# H-bridge.net
KiCad netlist of a schematic drawn in EAGLE
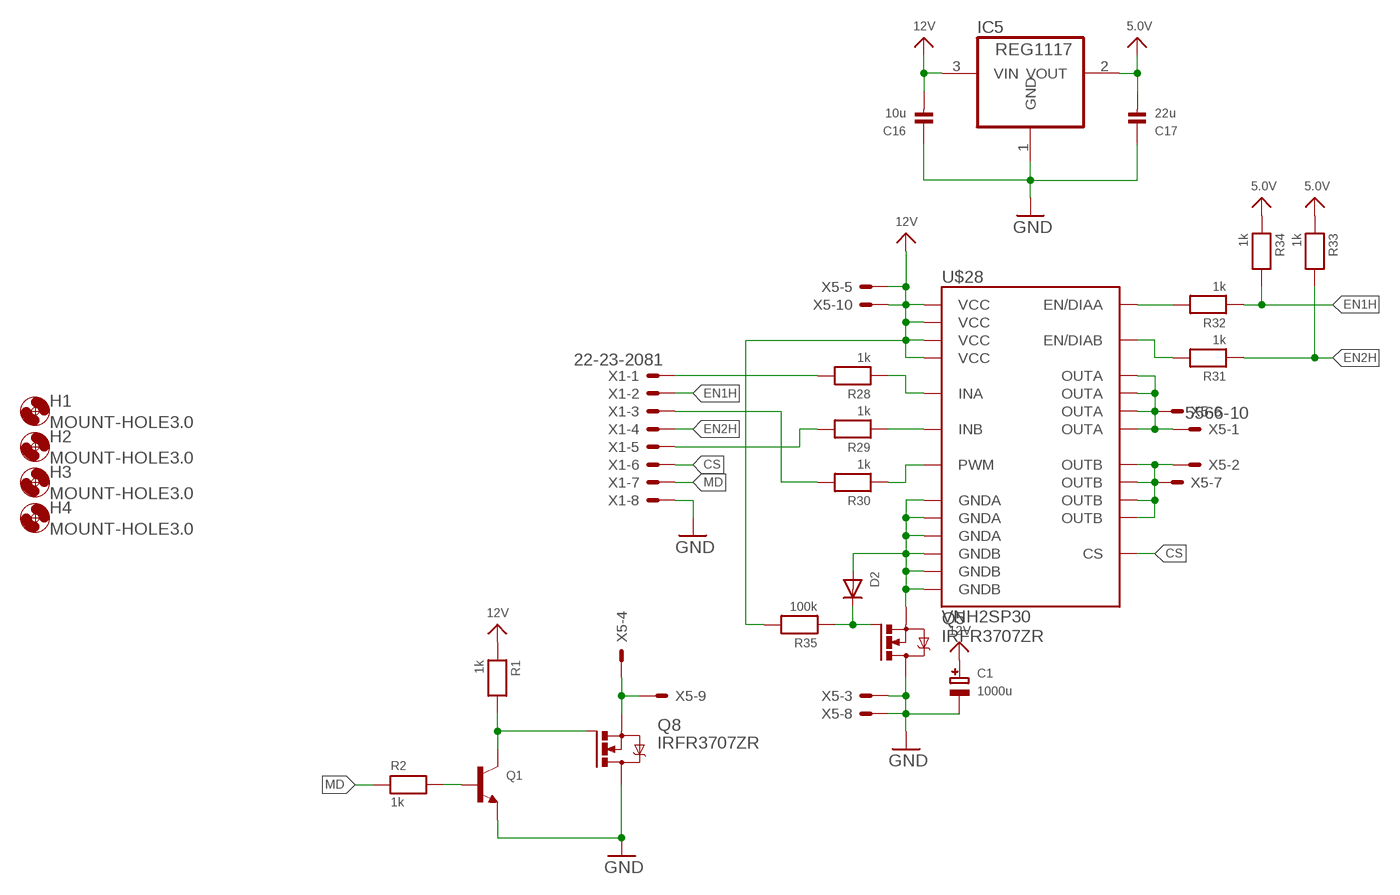
[diagram p0: schematic, sheet 1]

(export (version "E")
  (design (tool "Eeschema 10.0.6"))
  (components
    (comp (ref "C1")
      (value "1000u")
      (footprint "eagle-import:CELEC_3.5MM_10MM")
      (libsource (lib "eagle-import") (part "CAP_ELECTROLYTICPTH_3.5MMGRID_10MMDIA"))
    )
    (comp (ref "C16")
      (value "10u")
      (footprint "eagle-import:_0805")
      (libsource (lib "eagle-import") (part "CAP_CERAMIC_0805"))
    )
    (comp (ref "C17")
      (value "22u")
      (footprint "eagle-import:_0805")
      (libsource (lib "eagle-import") (part "CAP_CERAMIC_0805"))
    )
    (comp (ref "D2")
      (value "DIODESMA")
      (footprint "eagle-import:SMADIODE")
      (libsource (lib "eagle-import") (part "DIODESMA"))
    )
    (comp (ref "H1")
      (value "MOUNT-HOLE3.0")
      (footprint "eagle-import:3,0")
      (libsource (lib "eagle-import") (part "MOUNT-HOLE3.0"))
    )
    (comp (ref "H2")
      (value "MOUNT-HOLE3.0")
      (footprint "eagle-import:3,0")
      (libsource (lib "eagle-import") (part "MOUNT-HOLE3.0"))
    )
    (comp (ref "H3")
      (value "MOUNT-HOLE3.0")
      (footprint "eagle-import:3,0")
      (libsource (lib "eagle-import") (part "MOUNT-HOLE3.0"))
    )
    (comp (ref "H4")
      (value "MOUNT-HOLE3.0")
      (footprint "eagle-import:3,0")
      (libsource (lib "eagle-import") (part "MOUNT-HOLE3.0"))
    )
    (comp (ref "IC5")
      (value "REG1117")
      (footprint "eagle-import:SOT223")
      (libsource (lib "eagle-import") (part "REG1117"))
    )
    (comp (ref "Q1")
      (value "TRANSISTOR_NPNWIDE")
      (footprint "eagle-import:SOT23-WIDE")
      (libsource (lib "eagle-import") (part "TRANSISTOR_NPNWIDE"))
    )
    (comp (ref "Q5")
      (value "IRFR3707ZR")
      (footprint "eagle-import:D-PAK_TO252AA")
      (libsource (lib "eagle-import") (part "IRFR3707ZR"))
    )
    (comp (ref "Q8")
      (value "IRFR3707ZR")
      (footprint "eagle-import:D-PAK_TO252AA")
      (libsource (lib "eagle-import") (part "IRFR3707ZR"))
    )
    (comp (ref "R1")
      (value "1k")
      (footprint "eagle-import:_0603")
      (libsource (lib "eagle-import") (part "RESISTOR_0603"))
    )
    (comp (ref "R2")
      (value "1k")
      (footprint "eagle-import:_0603")
      (libsource (lib "eagle-import") (part "RESISTOR_0603"))
    )
    (comp (ref "R28")
      (value "1k")
      (footprint "eagle-import:_0603")
      (libsource (lib "eagle-import") (part "RESISTOR_0603"))
    )
    (comp (ref "R29")
      (value "1k")
      (footprint "eagle-import:_0603")
      (libsource (lib "eagle-import") (part "RESISTOR_0603"))
    )
    (comp (ref "R30")
      (value "1k")
      (footprint "eagle-import:_0603")
      (libsource (lib "eagle-import") (part "RESISTOR_0603"))
    )
    (comp (ref "R31")
      (value "1k")
      (footprint "eagle-import:_0603")
      (libsource (lib "eagle-import") (part "RESISTOR_0603"))
    )
    (comp (ref "R32")
      (value "1k")
      (footprint "eagle-import:_0603")
      (libsource (lib "eagle-import") (part "RESISTOR_0603"))
    )
    (comp (ref "R33")
      (value "1k")
      (footprint "eagle-import:_0603")
      (libsource (lib "eagle-import") (part "RESISTOR_0603"))
    )
    (comp (ref "R34")
      (value "1k")
      (footprint "eagle-import:_0603")
      (libsource (lib "eagle-import") (part "RESISTOR_0603"))
    )
    (comp (ref "R35")
      (value "100k")
      (footprint "eagle-import:_0603")
      (libsource (lib "eagle-import") (part "RESISTOR_0603"))
    )
    (comp (ref "U$28")
      (value "VNH2SP30")
      (footprint "eagle-import:VNH2SP30")
      (libsource (lib "eagle-import") (part "VNH2SP30"))
    )
    (comp (ref "X1")
      (value "22-23-2081")
      (footprint "eagle-import:22-23-2081")
      (fields (field (name "MF") "MOLEX"))
      (libsource (lib "eagle-import") (part "22-23-2081"))
    )
    (comp (ref "X5")
      (value "5566-10")
      (footprint "eagle-import:5566-10")
      (libsource (lib "eagle-import") (part "5566-10"))
    )
  )
  (nets
    (net (code "1") (name "5.0V") (class "Default")
      (node (ref "C17") (pin "2") (pinfunction "P$2_2") (pintype "passive"))
      (node (ref "IC5") (pin "2") (pinfunction "VOUT_2") (pintype "output"))
      (node (ref "R33") (pin "1") (pinfunction "1_1") (pintype "passive"))
      (node (ref "R34") (pin "1") (pinfunction "1_1") (pintype "passive"))
    )
    (net (code "2") (name "12V") (class "Default")
      (node (ref "C1") (pin "+") (pinfunction "+_+") (pintype "passive"))
      (node (ref "C16") (pin "2") (pinfunction "P$2_2") (pintype "passive"))
      (node (ref "IC5") (pin "3") (pinfunction "VIN_3") (pintype "input"))
      (node (ref "R1") (pin "1") (pinfunction "1_1") (pintype "passive"))
      (node (ref "R35") (pin "2") (pinfunction "2_2") (pintype "passive"))
      (node (ref "U$28") (pin "13") (pinfunction "VCC_13") (pintype "bidirectional"))
      (node (ref "U$28") (pin "23") (pinfunction "VCC_23") (pintype "bidirectional"))
      (node (ref "U$28") (pin "3") (pinfunction "VCC_3") (pintype "bidirectional"))
      (node (ref "U$28") (pin "SLUG1") (pinfunction "VCC_SLUG1") (pintype "bidirectional"))
      (node (ref "X5") (pin "10") (pinfunction "S_10") (pintype "passive"))
      (node (ref "X5") (pin "5") (pinfunction "S_5") (pintype "passive"))
    )
    (net (code "3") (name "CS") (class "Default")
      (node (ref "U$28") (pin "9") (pinfunction "CS_9") (pintype "bidirectional"))
      (node (ref "X1") (pin "6") (pinfunction "S_6") (pintype "passive"))
    )
    (net (code "4") (name "EN1H") (class "Default")
      (node (ref "R32") (pin "1") (pinfunction "1_1") (pintype "passive"))
      (node (ref "R34") (pin "2") (pinfunction "2_2") (pintype "passive"))
      (node (ref "X1") (pin "2") (pinfunction "S_2") (pintype "passive"))
    )
    (net (code "5") (name "EN2H") (class "Default")
      (node (ref "R31") (pin "1") (pinfunction "1_1") (pintype "passive"))
      (node (ref "R33") (pin "2") (pinfunction "2_2") (pintype "passive"))
      (node (ref "X1") (pin "4") (pinfunction "S_4") (pintype "passive"))
    )
    (net (code "6") (name "GND") (class "Default")
      (node (ref "C1") (pin "-") (pinfunction "-_-") (pintype "passive"))
      (node (ref "C16") (pin "1") (pinfunction "P$1_1") (pintype "passive"))
      (node (ref "C17") (pin "1") (pinfunction "P$1_1") (pintype "passive"))
      (node (ref "IC5") (pin "1") (pinfunction "GND_1") (pintype "power_in"))
      (node (ref "Q1") (pin "2") (pinfunction "E_2") (pintype "passive"))
      (node (ref "Q5") (pin "4") (pinfunction "D_4") (pintype "passive"))
      (node (ref "Q8") (pin "4") (pinfunction "D_4") (pintype "passive"))
      (node (ref "X1") (pin "8") (pinfunction "S_8") (pintype "passive"))
      (node (ref "X5") (pin "3") (pinfunction "S_3") (pintype "passive"))
      (node (ref "X5") (pin "8") (pinfunction "S_8") (pintype "passive"))
    )
    (net (code "7") (name "MD") (class "Default")
      (node (ref "R2") (pin "1") (pinfunction "1_1") (pintype "passive"))
      (node (ref "X1") (pin "7") (pinfunction "S_7") (pintype "passive"))
    )
    (net (code "8") (name "Net-(Q1-B)") (class "Default")
      (node (ref "Q1") (pin "1") (pinfunction "B_1") (pintype "passive"))
      (node (ref "R2") (pin "2") (pinfunction "2_2") (pintype "passive"))
    )
    (net (code "9") (name "Net-(Q1-C)") (class "Default")
      (node (ref "Q1") (pin "3") (pinfunction "C_3") (pintype "passive"))
      (node (ref "Q8") (pin "1") (pinfunction "G_1") (pintype "passive"))
      (node (ref "R1") (pin "2") (pinfunction "2_2") (pintype "passive"))
    )
    (net (code "10") (name "Net-(Q5-G)") (class "Default")
      (node (ref "D2") (pin "C") (pinfunction "C_C") (pintype "passive"))
      (node (ref "Q5") (pin "1") (pinfunction "G_1") (pintype "passive"))
      (node (ref "R35") (pin "1") (pinfunction "1_1") (pintype "passive"))
    )
    (net (code "11") (name "Net-(Q5-S)") (class "Default")
      (node (ref "D2") (pin "A") (pinfunction "A_A") (pintype "passive"))
      (node (ref "Q5") (pin "3") (pinfunction "S_3") (pintype "passive"))
      (node (ref "U$28") (pin "18") (pinfunction "GNDB_18") (pintype "bidirectional"))
      (node (ref "U$28") (pin "19") (pinfunction "GNDB_19") (pintype "bidirectional"))
      (node (ref "U$28") (pin "20") (pinfunction "GNDB_20") (pintype "bidirectional"))
      (node (ref "U$28") (pin "26") (pinfunction "GNDA_26") (pintype "bidirectional"))
      (node (ref "U$28") (pin "27") (pinfunction "GNDA_27") (pintype "bidirectional"))
      (node (ref "U$28") (pin "28") (pinfunction "GNDA_28") (pintype "bidirectional"))
    )
    (net (code "12") (name "Net-(Q8-S)") (class "Default")
      (node (ref "Q8") (pin "3") (pinfunction "S_3") (pintype "passive"))
      (node (ref "X5") (pin "4") (pinfunction "S_4") (pintype "passive"))
      (node (ref "X5") (pin "9") (pinfunction "S_9") (pintype "passive"))
    )
    (net (code "13") (name "Net-(U$28-EN{slash}DIAA)") (class "Default")
      (node (ref "R32") (pin "2") (pinfunction "2_2") (pintype "passive"))
      (node (ref "U$28") (pin "6") (pinfunction "EN/DIAA_6") (pintype "bidirectional"))
    )
    (net (code "14") (name "Net-(U$28-EN{slash}DIAB)") (class "Default")
      (node (ref "R31") (pin "2") (pinfunction "2_2") (pintype "passive"))
      (node (ref "U$28") (pin "10") (pinfunction "EN/DIAB_10") (pintype "bidirectional"))
    )
    (net (code "15") (name "Net-(U$28-INA)") (class "Default")
      (node (ref "R28") (pin "1") (pinfunction "1_1") (pintype "passive"))
      (node (ref "U$28") (pin "5") (pinfunction "INA_5") (pintype "bidirectional"))
    )
    (net (code "16") (name "Net-(U$28-INB)") (class "Default")
      (node (ref "R29") (pin "1") (pinfunction "1_1") (pintype "passive"))
      (node (ref "U$28") (pin "11") (pinfunction "INB_11") (pintype "bidirectional"))
    )
    (net (code "17") (name "Net-(U$28-PWM)") (class "Default")
      (node (ref "R30") (pin "1") (pinfunction "1_1") (pintype "passive"))
      (node (ref "U$28") (pin "8") (pinfunction "PWM_8") (pintype "bidirectional"))
    )
    (net (code "18") (name "Net-(X1A-S)") (class "Default")
      (node (ref "R28") (pin "2") (pinfunction "2_2") (pintype "passive"))
      (node (ref "X1") (pin "1") (pinfunction "S_1") (pintype "passive"))
    )
    (net (code "19") (name "Net-(X1C-S)") (class "Default")
      (node (ref "R30") (pin "2") (pinfunction "2_2") (pintype "passive"))
      (node (ref "X1") (pin "3") (pinfunction "S_3") (pintype "passive"))
    )
    (net (code "20") (name "Net-(X1E-S)") (class "Default")
      (node (ref "R29") (pin "2") (pinfunction "2_2") (pintype "passive"))
      (node (ref "X1") (pin "5") (pinfunction "S_5") (pintype "passive"))
    )
    (net (code "21") (name "Net-(X5A-S)") (class "Default")
      (node (ref "U$28") (pin "1") (pinfunction "OUTA_1") (pintype "bidirectional"))
      (node (ref "U$28") (pin "25") (pinfunction "OUTA_25") (pintype "bidirectional"))
      (node (ref "U$28") (pin "30") (pinfunction "OUTA_30") (pintype "bidirectional"))
      (node (ref "U$28") (pin "SLUG3") (pinfunction "OUTA_SLUG3") (pintype "bidirectional"))
      (node (ref "X5") (pin "1") (pinfunction "S_1") (pintype "passive"))
      (node (ref "X5") (pin "6") (pinfunction "S_6") (pintype "passive"))
    )
    (net (code "22") (name "Net-(X5C-S)") (class "Default")
      (node (ref "U$28") (pin "15") (pinfunction "OUTB_15") (pintype "bidirectional"))
      (node (ref "U$28") (pin "16") (pinfunction "OUTB_16") (pintype "bidirectional"))
      (node (ref "U$28") (pin "21") (pinfunction "OUTB_21") (pintype "bidirectional"))
      (node (ref "U$28") (pin "SLUG2") (pinfunction "OUTB_SLUG2") (pintype "bidirectional"))
      (node (ref "X5") (pin "2") (pinfunction "S_2") (pintype "passive"))
      (node (ref "X5") (pin "7") (pinfunction "S_7") (pintype "passive"))
    )
  )
)
